# MCP73871.net
KiCad netlist of a schematic drawn in EAGLE
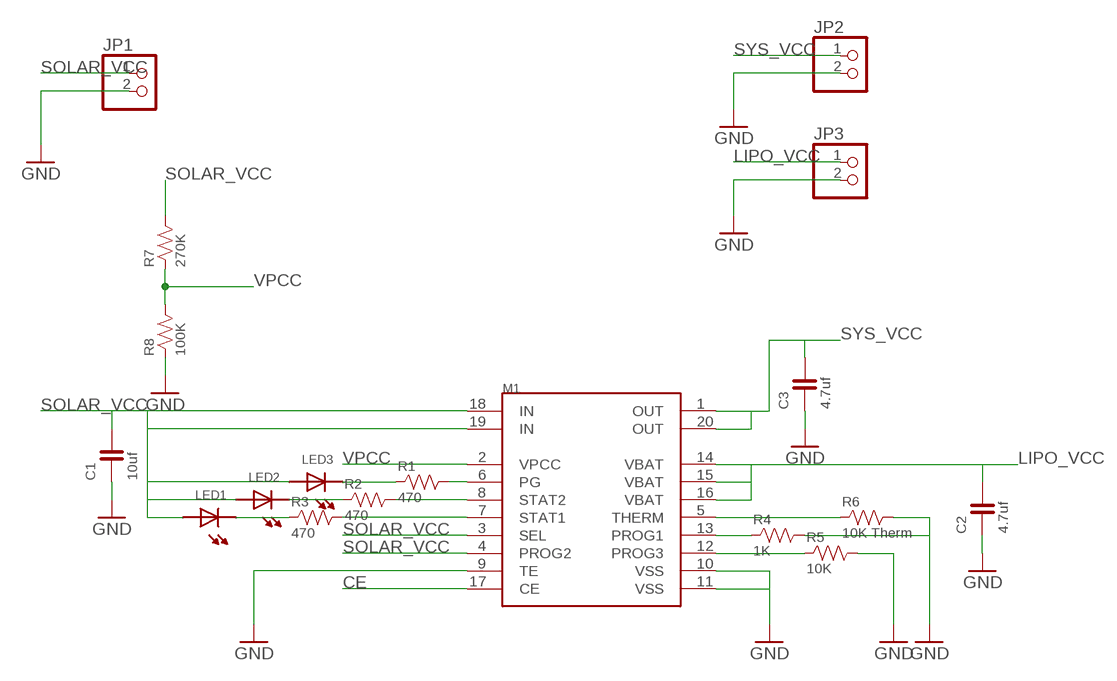
[diagram p0: schematic, sheet 1]

(export (version "E")
  (design (tool "Eeschema 10.0.6"))
  (components
    (comp (ref "C1")
      (value "10uf")
      (footprint "eagle-import:0603")
      (libsource (lib "eagle-import") (part "CAPACITOR-0603"))
    )
    (comp (ref "C2")
      (value "4.7uf")
      (footprint "eagle-import:0603")
      (libsource (lib "eagle-import") (part "CAPACITOR-0603"))
    )
    (comp (ref "C3")
      (value "4.7uf")
      (footprint "eagle-import:0603")
      (libsource (lib "eagle-import") (part "CAPACITOR-0603"))
    )
    (comp (ref "JP1")
      (value "PINHD-1X2")
      (footprint "eagle-import:1X02")
      (libsource (lib "eagle-import") (part "PINHD-1X2"))
    )
    (comp (ref "JP2")
      (value "PINHD-1X2")
      (footprint "eagle-import:1X02")
      (libsource (lib "eagle-import") (part "PINHD-1X2"))
    )
    (comp (ref "JP3")
      (value "PINHD-1X2")
      (footprint "eagle-import:1X02")
      (libsource (lib "eagle-import") (part "PINHD-1X2"))
    )
    (comp (ref "LED1")
      (value "LED-0603")
      (footprint "eagle-import:0603")
      (libsource (lib "eagle-import") (part "LED-0603"))
    )
    (comp (ref "LED2")
      (value "LED-0603")
      (footprint "eagle-import:0603")
      (libsource (lib "eagle-import") (part "LED-0603"))
    )
    (comp (ref "LED3")
      (value "LED-0603")
      (footprint "eagle-import:0603")
      (libsource (lib "eagle-import") (part "LED-0603"))
    )
    (comp (ref "M1")
      (value "MCP73871")
      (footprint "eagle-import:QFN")
      (libsource (lib "eagle-import") (part "MCP73871"))
    )
    (comp (ref "R1")
      (value "470")
      (footprint "eagle-import:0603")
      (libsource (lib "eagle-import") (part "RESISTOR-0603"))
    )
    (comp (ref "R2")
      (value "470")
      (footprint "eagle-import:0603")
      (libsource (lib "eagle-import") (part "RESISTOR-0603"))
    )
    (comp (ref "R3")
      (value "470")
      (footprint "eagle-import:0603")
      (libsource (lib "eagle-import") (part "RESISTOR-0603"))
    )
    (comp (ref "R4")
      (value "1K")
      (footprint "eagle-import:0603")
      (libsource (lib "eagle-import") (part "RESISTOR-0603"))
    )
    (comp (ref "R5")
      (value "10K")
      (footprint "eagle-import:0603")
      (libsource (lib "eagle-import") (part "RESISTOR-0603"))
    )
    (comp (ref "R6")
      (value "10K Therm")
      (footprint "eagle-import:0603")
      (libsource (lib "eagle-import") (part "RESISTOR-0603"))
    )
    (comp (ref "R7")
      (value "270K")
      (footprint "eagle-import:0603")
      (libsource (lib "eagle-import") (part "RESISTOR-0603"))
    )
    (comp (ref "R8")
      (value "100K")
      (footprint "eagle-import:0603")
      (libsource (lib "eagle-import") (part "RESISTOR-0603"))
    )
  )
  (nets
    (net (code "1") (name "/CE") (class "Default")
      (node (ref "M1") (pin "17") (pinfunction "CE_17") (pintype "bidirectional"))
    )
    (net (code "2") (name "/LIPO_VCC") (class "Default")
      (node (ref "C2") (pin "2") (pinfunction "2_2") (pintype "passive"))
      (node (ref "JP3") (pin "1") (pinfunction "1_1") (pintype "passive"))
      (node (ref "M1") (pin "14") (pinfunction "VBAT_14") (pintype "bidirectional"))
      (node (ref "M1") (pin "15") (pinfunction "VBAT_15") (pintype "bidirectional"))
      (node (ref "M1") (pin "16") (pinfunction "VBAT_16") (pintype "bidirectional"))
    )
    (net (code "3") (name "/SOLAR_VCC") (class "Default")
      (node (ref "C1") (pin "2") (pinfunction "2_2") (pintype "passive"))
      (node (ref "JP1") (pin "1") (pinfunction "1_1") (pintype "passive"))
      (node (ref "LED1") (pin "ANODE") (pinfunction "ANODE_ANODE") (pintype "passive"))
      (node (ref "LED2") (pin "ANODE") (pinfunction "ANODE_ANODE") (pintype "passive"))
      (node (ref "LED3") (pin "ANODE") (pinfunction "ANODE_ANODE") (pintype "passive"))
      (node (ref "M1") (pin "18") (pinfunction "IN_18") (pintype "bidirectional"))
      (node (ref "M1") (pin "19") (pinfunction "IN_19") (pintype "bidirectional"))
      (node (ref "M1") (pin "3") (pinfunction "SEL_3") (pintype "bidirectional"))
      (node (ref "M1") (pin "4") (pinfunction "PROG2_4") (pintype "bidirectional"))
      (node (ref "R7") (pin "2") (pinfunction "2_2") (pintype "bidirectional"))
    )
    (net (code "4") (name "/SYS_VCC") (class "Default")
      (node (ref "C3") (pin "2") (pinfunction "2_2") (pintype "passive"))
      (node (ref "JP2") (pin "1") (pinfunction "1_1") (pintype "passive"))
      (node (ref "M1") (pin "1") (pinfunction "OUT_1") (pintype "bidirectional"))
      (node (ref "M1") (pin "20") (pinfunction "OUT_20") (pintype "bidirectional"))
    )
    (net (code "5") (name "/VPCC") (class "Default")
      (node (ref "M1") (pin "2") (pinfunction "VPCC_2") (pintype "bidirectional"))
      (node (ref "R7") (pin "1") (pinfunction "1_1") (pintype "bidirectional"))
      (node (ref "R8") (pin "2") (pinfunction "2_2") (pintype "bidirectional"))
    )
    (net (code "6") (name "GND") (class "Default")
      (node (ref "C1") (pin "1") (pinfunction "1_1") (pintype "passive"))
      (node (ref "C2") (pin "1") (pinfunction "1_1") (pintype "passive"))
      (node (ref "C3") (pin "1") (pinfunction "1_1") (pintype "passive"))
      (node (ref "JP1") (pin "2") (pinfunction "2_2") (pintype "passive"))
      (node (ref "JP2") (pin "2") (pinfunction "2_2") (pintype "passive"))
      (node (ref "JP3") (pin "2") (pinfunction "2_2") (pintype "passive"))
      (node (ref "M1") (pin "10") (pinfunction "VSS_10") (pintype "bidirectional"))
      (node (ref "M1") (pin "11") (pinfunction "VSS_11") (pintype "bidirectional"))
      (node (ref "M1") (pin "9") (pinfunction "TE_9") (pintype "bidirectional"))
      (node (ref "R4") (pin "2") (pinfunction "2_2") (pintype "bidirectional"))
      (node (ref "R5") (pin "2") (pinfunction "2_2") (pintype "bidirectional"))
      (node (ref "R6") (pin "2") (pinfunction "2_2") (pintype "bidirectional"))
      (node (ref "R8") (pin "1") (pinfunction "1_1") (pintype "bidirectional"))
    )
    (net (code "7") (name "Net-(LED1-PadCATHODE)") (class "Default")
      (node (ref "LED1") (pin "CATHODE") (pinfunction "CATHODE_CATHODE") (pintype "passive"))
      (node (ref "R3") (pin "1") (pinfunction "1_1") (pintype "bidirectional"))
    )
    (net (code "8") (name "Net-(LED2-PadCATHODE)") (class "Default")
      (node (ref "LED2") (pin "CATHODE") (pinfunction "CATHODE_CATHODE") (pintype "passive"))
      (node (ref "R2") (pin "1") (pinfunction "1_1") (pintype "bidirectional"))
    )
    (net (code "9") (name "Net-(LED3-PadCATHODE)") (class "Default")
      (node (ref "LED3") (pin "CATHODE") (pinfunction "CATHODE_CATHODE") (pintype "passive"))
      (node (ref "R1") (pin "1") (pinfunction "1_1") (pintype "bidirectional"))
    )
    (net (code "10") (name "Net-(M1-PG)") (class "Default")
      (node (ref "M1") (pin "6") (pinfunction "PG_6") (pintype "bidirectional"))
      (node (ref "R1") (pin "2") (pinfunction "2_2") (pintype "bidirectional"))
    )
    (net (code "11") (name "Net-(M1-PROG1)") (class "Default")
      (node (ref "M1") (pin "13") (pinfunction "PROG1_13") (pintype "bidirectional"))
      (node (ref "R4") (pin "1") (pinfunction "1_1") (pintype "bidirectional"))
    )
    (net (code "12") (name "Net-(M1-PROG3)") (class "Default")
      (node (ref "M1") (pin "12") (pinfunction "PROG3_12") (pintype "bidirectional"))
      (node (ref "R5") (pin "1") (pinfunction "1_1") (pintype "bidirectional"))
    )
    (net (code "13") (name "Net-(M1-STAT1)") (class "Default")
      (node (ref "M1") (pin "7") (pinfunction "STAT1_7") (pintype "bidirectional"))
      (node (ref "R3") (pin "2") (pinfunction "2_2") (pintype "bidirectional"))
    )
    (net (code "14") (name "Net-(M1-STAT2)") (class "Default")
      (node (ref "M1") (pin "8") (pinfunction "STAT2_8") (pintype "bidirectional"))
      (node (ref "R2") (pin "2") (pinfunction "2_2") (pintype "bidirectional"))
    )
    (net (code "15") (name "Net-(M1-THERM)") (class "Default")
      (node (ref "M1") (pin "5") (pinfunction "THERM_5") (pintype "bidirectional"))
      (node (ref "R6") (pin "1") (pinfunction "1_1") (pintype "bidirectional"))
    )
  )
)
